# INPUT.net
KiCad netlist of a schematic drawn in Altium Designer
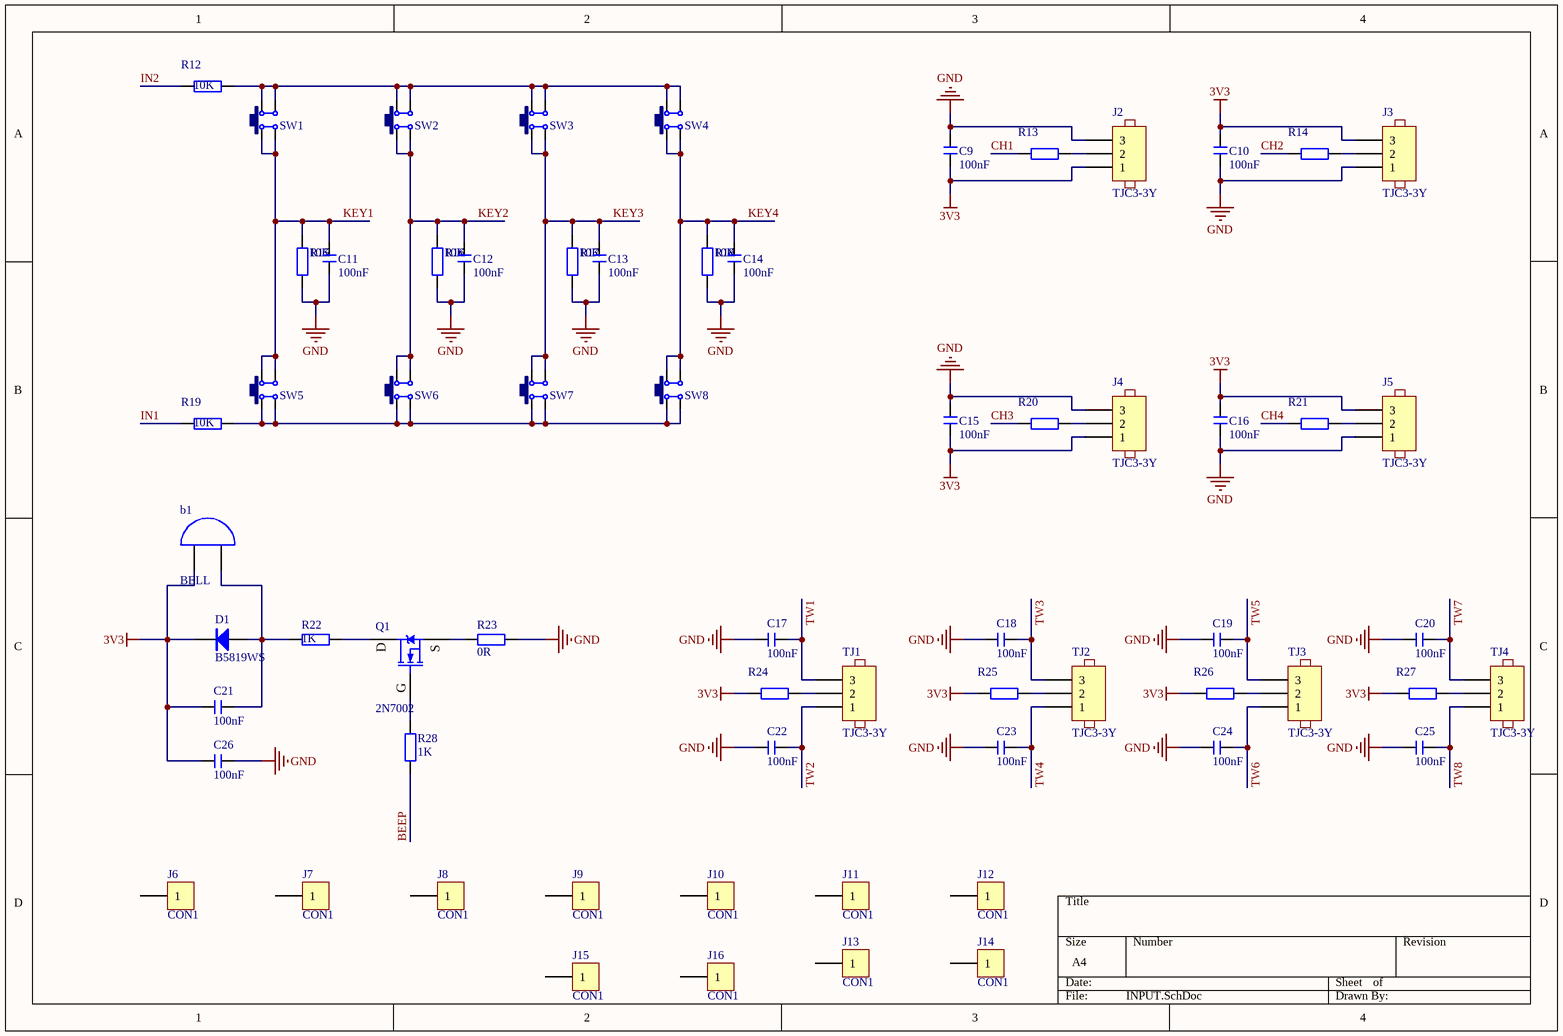
[diagram p0: INPUT.SchDoc]

(export (version "E")
  (design (tool "Eeschema 10.0.6"))
  (components
    (comp (ref "b1") (value "BELL") (footprint "BEEP 5x9x5.5") (libsource (lib "常用元件库") (part "BELL")))
    (comp (ref "C9")
      (value "100nF")
      (footprint "C 0603_L")
      (description "无极性贴片电容")
      (fields (field (name "版权归属") "源创客"))
      (libsource (lib "3.1   - 电阻-电容-电感") (part "C"))
    )
    (comp (ref "C10")
      (value "100nF")
      (footprint "C 0603_L")
      (description "无极性贴片电容")
      (fields (field (name "版权归属") "源创客"))
      (libsource (lib "3.1   - 电阻-电容-电感") (part "C"))
    )
    (comp (ref "C11")
      (value "100nF")
      (footprint "C 0603_L")
      (description "无极性贴片电容")
      (fields (field (name "版权归属") "源创客"))
      (libsource (lib "3.1   - 电阻-电容-电感") (part "C"))
    )
    (comp (ref "C12")
      (value "100nF")
      (footprint "C 0603_L")
      (description "无极性贴片电容")
      (fields (field (name "版权归属") "源创客"))
      (libsource (lib "3.1   - 电阻-电容-电感") (part "C"))
    )
    (comp (ref "C13")
      (value "100nF")
      (footprint "C 0603_L")
      (description "无极性贴片电容")
      (fields (field (name "版权归属") "源创客"))
      (libsource (lib "3.1   - 电阻-电容-电感") (part "C"))
    )
    (comp (ref "C14")
      (value "100nF")
      (footprint "C 0603_L")
      (description "无极性贴片电容")
      (fields (field (name "版权归属") "源创客"))
      (libsource (lib "3.1   - 电阻-电容-电感") (part "C"))
    )
    (comp (ref "C15")
      (value "100nF")
      (footprint "C 0603_L")
      (description "无极性贴片电容")
      (fields (field (name "版权归属") "源创客"))
      (libsource (lib "3.1   - 电阻-电容-电感") (part "C"))
    )
    (comp (ref "C16")
      (value "100nF")
      (footprint "C 0603_L")
      (description "无极性贴片电容")
      (fields (field (name "版权归属") "源创客"))
      (libsource (lib "3.1   - 电阻-电容-电感") (part "C"))
    )
    (comp (ref "C17")
      (value "100nF")
      (footprint "C 0603_L")
      (description "无极性贴片电容")
      (fields (field (name "版权归属") "源创客"))
      (libsource (lib "3.1   - 电阻-电容-电感") (part "C"))
    )
    (comp (ref "C18")
      (value "100nF")
      (footprint "C 0603_L")
      (description "无极性贴片电容")
      (fields (field (name "版权归属") "源创客"))
      (libsource (lib "3.1   - 电阻-电容-电感") (part "C"))
    )
    (comp (ref "C19")
      (value "100nF")
      (footprint "C 0603_L")
      (description "无极性贴片电容")
      (fields (field (name "版权归属") "源创客"))
      (libsource (lib "3.1   - 电阻-电容-电感") (part "C"))
    )
    (comp (ref "C20")
      (value "100nF")
      (footprint "C 0603_L")
      (description "无极性贴片电容")
      (fields (field (name "版权归属") "源创客"))
      (libsource (lib "3.1   - 电阻-电容-电感") (part "C"))
    )
    (comp (ref "C21")
      (value "100nF")
      (footprint "C 0603_L")
      (description "无极性贴片电容")
      (fields (field (name "版权归属") "源创客"))
      (libsource (lib "3.1   - 电阻-电容-电感") (part "C"))
    )
    (comp (ref "C22")
      (value "100nF")
      (footprint "C 0603_L")
      (description "无极性贴片电容")
      (fields (field (name "版权归属") "源创客"))
      (libsource (lib "3.1   - 电阻-电容-电感") (part "C"))
    )
    (comp (ref "C23")
      (value "100nF")
      (footprint "C 0603_L")
      (description "无极性贴片电容")
      (fields (field (name "版权归属") "源创客"))
      (libsource (lib "3.1   - 电阻-电容-电感") (part "C"))
    )
    (comp (ref "C24")
      (value "100nF")
      (footprint "C 0603_L")
      (description "无极性贴片电容")
      (fields (field (name "版权归属") "源创客"))
      (libsource (lib "3.1   - 电阻-电容-电感") (part "C"))
    )
    (comp (ref "C25")
      (value "100nF")
      (footprint "C 0603_L")
      (description "无极性贴片电容")
      (fields (field (name "版权归属") "源创客"))
      (libsource (lib "3.1   - 电阻-电容-电感") (part "C"))
    )
    (comp (ref "C26")
      (value "100nF")
      (footprint "C 0603_L")
      (description "无极性贴片电容")
      (fields (field (name "版权归属") "源创客"))
      (libsource (lib "3.1   - 电阻-电容-电感") (part "C"))
    )
    (comp (ref "D1")
      (value "B5819WS")
      (footprint "SOD-323")
      (description "肖特基二极管                           电压:40V 电流:1A                 C7420331")
      (fields (field (name "版权归属") "源创客"))
      (libsource (lib "8.1   - 二极管-整流桥") (part "SR540"))
    )
    (comp (ref "J2")
      (value "TJC3-3Y")
      (footprint "MX 1.25-LS-3P")
      (description "HCZZ0015-3             C7433469")
      (fields (field (name "PUBLISHER") "Altium Limited"))
      (libsource (lib "接口与插座") (part "TJC3-3Y"))
    )
    (comp (ref "J3")
      (value "TJC3-3Y")
      (footprint "MX 1.25-LS-3P")
      (description "HCZZ0015-3             C7433469")
      (fields (field (name "PUBLISHER") "Altium Limited"))
      (libsource (lib "接口与插座") (part "TJC3-3Y"))
    )
    (comp (ref "J4")
      (value "TJC3-3Y")
      (footprint "MX 1.25-LS-3P")
      (description "HCZZ0015-3             C7433469")
      (fields (field (name "PUBLISHER") "Altium Limited"))
      (libsource (lib "接口与插座") (part "TJC3-3Y"))
    )
    (comp (ref "J5")
      (value "TJC3-3Y")
      (footprint "MX 1.25-LS-3P")
      (description "HCZZ0015-3             C7433469")
      (fields (field (name "PUBLISHER") "Altium Limited"))
      (libsource (lib "接口与插座") (part "TJC3-3Y"))
    )
    (comp (ref "J6") (value "CON1") (footprint "M3x5+6_L") (libsource (lib "常用元件库") (part "CON1")))
    (comp (ref "J7") (value "CON1") (footprint "M3x5+6_L") (libsource (lib "常用元件库") (part "CON1")))
    (comp (ref "J8") (value "CON1") (footprint "M3x5+6_L") (libsource (lib "常用元件库") (part "CON1")))
    (comp (ref "J9") (value "CON1") (footprint "M3x5+6_L") (libsource (lib "常用元件库") (part "CON1")))
    (comp (ref "J10") (value "CON1") (footprint "M3x5+6_L") (libsource (lib "常用元件库") (part "CON1")))
    (comp (ref "J11") (value "CON1") (footprint "M3x5+6_L") (libsource (lib "常用元件库") (part "CON1")))
    (comp (ref "J12") (value "CON1") (footprint "M3x5+6_L") (libsource (lib "常用元件库") (part "CON1")))
    (comp (ref "J13") (value "CON1") (footprint "M3x5+6_L") (libsource (lib "常用元件库") (part "CON1")))
    (comp (ref "J14") (value "CON1") (footprint "M3x5+6_L") (libsource (lib "常用元件库") (part "CON1")))
    (comp (ref "J15") (value "CON1") (footprint "M3x5+6_L") (libsource (lib "常用元件库") (part "CON1")))
    (comp (ref "J16") (value "CON1") (footprint "M3x5+6_L") (libsource (lib "常用元件库") (part "CON1")))
    (comp (ref "Q1")
      (value "2N7002")
      (footprint "SOT-23")
      (description "N沟场效应管")
      (fields (field (name "版权归属") "源创客"))
      (libsource (lib "6.1   - 场效应管-可控硅") (part "IRF840"))
    )
    (comp (ref "R12")
      (value "10K")
      (footprint "R 0603_L")
      (description "贴片电阻")
      (fields (field (name "版权归属") "源创客"))
      (libsource (lib "3.1   - 电阻-电容-电感") (part "R"))
    )
    (comp (ref "R13")
      (value "~")
      (footprint "R 0603_L")
      (description "贴片电阻")
      (fields (field (name "版权归属") "源创客"))
      (libsource (lib "3.1   - 电阻-电容-电感") (part "R"))
    )
    (comp (ref "R14")
      (value "~")
      (footprint "R 0603_L")
      (description "贴片电阻")
      (fields (field (name "版权归属") "源创客"))
      (libsource (lib "3.1   - 电阻-电容-电感") (part "R"))
    )
    (comp (ref "R15")
      (value "10K")
      (footprint "R 0603_L")
      (description "贴片电阻")
      (fields (field (name "版权归属") "源创客"))
      (libsource (lib "3.1   - 电阻-电容-电感") (part "R"))
    )
    (comp (ref "R16")
      (value "10K")
      (footprint "R 0603_L")
      (description "贴片电阻")
      (fields (field (name "版权归属") "源创客"))
      (libsource (lib "3.1   - 电阻-电容-电感") (part "R"))
    )
    (comp (ref "R17")
      (value "10K")
      (footprint "R 0603_L")
      (description "贴片电阻")
      (fields (field (name "版权归属") "源创客"))
      (libsource (lib "3.1   - 电阻-电容-电感") (part "R"))
    )
    (comp (ref "R18")
      (value "10K")
      (footprint "R 0603_L")
      (description "贴片电阻")
      (fields (field (name "版权归属") "源创客"))
      (libsource (lib "3.1   - 电阻-电容-电感") (part "R"))
    )
    (comp (ref "R19")
      (value "10K")
      (footprint "R 0603_L")
      (description "贴片电阻")
      (fields (field (name "版权归属") "源创客"))
      (libsource (lib "3.1   - 电阻-电容-电感") (part "R"))
    )
    (comp (ref "R20")
      (value "~")
      (footprint "R 0603_L")
      (description "贴片电阻")
      (fields (field (name "版权归属") "源创客"))
      (libsource (lib "3.1   - 电阻-电容-电感") (part "R"))
    )
    (comp (ref "R21")
      (value "~")
      (footprint "R 0603_L")
      (description "贴片电阻")
      (fields (field (name "版权归属") "源创客"))
      (libsource (lib "3.1   - 电阻-电容-电感") (part "R"))
    )
    (comp (ref "R22")
      (value "1K")
      (footprint "R 0603_L")
      (description "贴片电阻")
      (fields (field (name "版权归属") "源创客"))
      (libsource (lib "3.1   - 电阻-电容-电感") (part "R"))
    )
    (comp (ref "R23")
      (value "0R")
      (footprint "R 0603_L")
      (description "贴片电阻")
      (fields (field (name "版权归属") "源创客"))
      (libsource (lib "3.1   - 电阻-电容-电感") (part "R"))
    )
    (comp (ref "R24")
      (value "~")
      (footprint "R 0603_L")
      (description "贴片电阻")
      (fields (field (name "版权归属") "源创客"))
      (libsource (lib "3.1   - 电阻-电容-电感") (part "R"))
    )
    (comp (ref "R25")
      (value "~")
      (footprint "R 0603_L")
      (description "贴片电阻")
      (fields (field (name "版权归属") "源创客"))
      (libsource (lib "3.1   - 电阻-电容-电感") (part "R"))
    )
    (comp (ref "R26")
      (value "~")
      (footprint "R 0603_L")
      (description "贴片电阻")
      (fields (field (name "版权归属") "源创客"))
      (libsource (lib "3.1   - 电阻-电容-电感") (part "R"))
    )
    (comp (ref "R27")
      (value "~")
      (footprint "R 0603_L")
      (description "贴片电阻")
      (fields (field (name "版权归属") "源创客"))
      (libsource (lib "3.1   - 电阻-电容-电感") (part "R"))
    )
    (comp (ref "R28")
      (value "1K")
      (footprint "R 0603_L")
      (description "贴片电阻")
      (fields (field (name "版权归属") "源创客"))
      (libsource (lib "3.1   - 电阻-电容-电感") (part "R"))
    )
    (comp (ref "SW1")
      (value "6x6x5")
      (footprint "TSW SMD-6*6*5-L")
      (description "KH-6X6X5H-STM     C2837531")
      (fields (field (name "版权归属") "源创客"))
      (libsource (lib "5.1   - 按键-开关") (part "TSW SMD-6x6"))
    )
    (comp (ref "SW2")
      (value "6x6x5")
      (footprint "TSW SMD-6*6*5-L")
      (description "KH-6X6X5H-STM     C2837531")
      (fields (field (name "版权归属") "源创客"))
      (libsource (lib "5.1   - 按键-开关") (part "TSW SMD-6x6"))
    )
    (comp (ref "SW3")
      (value "6x6x5")
      (footprint "TSW SMD-6*6*5-L")
      (description "KH-6X6X5H-STM     C2837531")
      (fields (field (name "版权归属") "源创客"))
      (libsource (lib "5.1   - 按键-开关") (part "TSW SMD-6x6"))
    )
    (comp (ref "SW4")
      (value "6x6x5")
      (footprint "TSW SMD-6*6*5-L")
      (description "KH-6X6X5H-STM     C2837531")
      (fields (field (name "版权归属") "源创客"))
      (libsource (lib "5.1   - 按键-开关") (part "TSW SMD-6x6"))
    )
    (comp (ref "SW5")
      (value "6x6x5")
      (footprint "TSW SMD-6*6*5-L")
      (description "KH-6X6X5H-STM     C2837531")
      (fields (field (name "版权归属") "源创客"))
      (libsource (lib "5.1   - 按键-开关") (part "TSW SMD-6x6"))
    )
    (comp (ref "SW6")
      (value "6x6x5")
      (footprint "TSW SMD-6*6*5-L")
      (description "KH-6X6X5H-STM     C2837531")
      (fields (field (name "版权归属") "源创客"))
      (libsource (lib "5.1   - 按键-开关") (part "TSW SMD-6x6"))
    )
    (comp (ref "SW7")
      (value "6x6x5")
      (footprint "TSW SMD-6*6*5-L")
      (description "KH-6X6X5H-STM     C2837531")
      (fields (field (name "版权归属") "源创客"))
      (libsource (lib "5.1   - 按键-开关") (part "TSW SMD-6x6"))
    )
    (comp (ref "SW8")
      (value "6x6x5")
      (footprint "TSW SMD-6*6*5-L")
      (description "KH-6X6X5H-STM     C2837531")
      (fields (field (name "版权归属") "源创客"))
      (libsource (lib "5.1   - 按键-开关") (part "TSW SMD-6x6"))
    )
    (comp (ref "TJ1")
      (value "TJC3-3Y")
      (footprint "MX 1.25-LS-3P")
      (description "HCZZ0015-3             C7433469")
      (fields (field (name "PUBLISHER") "Altium Limited"))
      (libsource (lib "接口与插座") (part "TJC3-3Y"))
    )
    (comp (ref "TJ2")
      (value "TJC3-3Y")
      (footprint "MX 1.25-LS-3P")
      (description "HCZZ0015-3             C7433469")
      (fields (field (name "PUBLISHER") "Altium Limited"))
      (libsource (lib "接口与插座") (part "TJC3-3Y"))
    )
    (comp (ref "TJ3")
      (value "TJC3-3Y")
      (footprint "MX 1.25-LS-3P")
      (description "HCZZ0015-3             C7433469")
      (fields (field (name "PUBLISHER") "Altium Limited"))
      (libsource (lib "接口与插座") (part "TJC3-3Y"))
    )
    (comp (ref "TJ4")
      (value "TJC3-3Y")
      (footprint "MX 1.25-LS-3P")
      (description "HCZZ0015-3             C7433469")
      (fields (field (name "PUBLISHER") "Altium Limited"))
      (libsource (lib "接口与插座") (part "TJC3-3Y"))
    )
  )
  (nets
    (net (code "1") (name "/BEEP") (class "Default")
      (node (ref "R28") (pin "1") (pinfunction "1_1") (pintype "passive"))
    )
    (net (code "2") (name "/CH1") (class "Default")
      (node (ref "R13") (pin "2") (pinfunction "2_2") (pintype "passive"))
    )
    (net (code "3") (name "/CH2") (class "Default")
      (node (ref "R14") (pin "2") (pinfunction "2_2") (pintype "passive"))
    )
    (net (code "4") (name "/CH3") (class "Default")
      (node (ref "R20") (pin "2") (pinfunction "2_2") (pintype "passive"))
    )
    (net (code "5") (name "/CH4") (class "Default")
      (node (ref "R21") (pin "2") (pinfunction "2_2") (pintype "passive"))
    )
    (net (code "6") (name "/IN1") (class "Default")
      (node (ref "R19") (pin "2") (pinfunction "2_2") (pintype "passive"))
    )
    (net (code "7") (name "/IN2") (class "Default")
      (node (ref "R12") (pin "2") (pinfunction "2_2") (pintype "passive"))
    )
    (net (code "8") (name "/KEY1") (class "Default")
      (node (ref "C11") (pin "2") (pinfunction "2_2") (pintype "passive"))
      (node (ref "R15") (pin "1") (pinfunction "1_1") (pintype "passive"))
      (node (ref "SW1") (pin "1") (pinfunction "1_1") (pintype "passive"))
      (node (ref "SW1") (pin "4") (pinfunction "4_4") (pintype "passive"))
      (node (ref "SW5") (pin "2") (pinfunction "2_2") (pintype "passive"))
      (node (ref "SW5") (pin "3") (pinfunction "3_3") (pintype "passive"))
    )
    (net (code "9") (name "/KEY2") (class "Default")
      (node (ref "C12") (pin "2") (pinfunction "2_2") (pintype "passive"))
      (node (ref "R16") (pin "1") (pinfunction "1_1") (pintype "passive"))
      (node (ref "SW2") (pin "1") (pinfunction "1_1") (pintype "passive"))
      (node (ref "SW2") (pin "4") (pinfunction "4_4") (pintype "passive"))
      (node (ref "SW6") (pin "2") (pinfunction "2_2") (pintype "passive"))
      (node (ref "SW6") (pin "3") (pinfunction "3_3") (pintype "passive"))
    )
    (net (code "10") (name "/KEY3") (class "Default")
      (node (ref "C13") (pin "2") (pinfunction "2_2") (pintype "passive"))
      (node (ref "R17") (pin "1") (pinfunction "1_1") (pintype "passive"))
      (node (ref "SW3") (pin "1") (pinfunction "1_1") (pintype "passive"))
      (node (ref "SW3") (pin "4") (pinfunction "4_4") (pintype "passive"))
      (node (ref "SW7") (pin "2") (pinfunction "2_2") (pintype "passive"))
      (node (ref "SW7") (pin "3") (pinfunction "3_3") (pintype "passive"))
    )
    (net (code "11") (name "/KEY4") (class "Default")
      (node (ref "C14") (pin "2") (pinfunction "2_2") (pintype "passive"))
      (node (ref "R18") (pin "1") (pinfunction "1_1") (pintype "passive"))
      (node (ref "SW4") (pin "1") (pinfunction "1_1") (pintype "passive"))
      (node (ref "SW4") (pin "4") (pinfunction "4_4") (pintype "passive"))
      (node (ref "SW8") (pin "2") (pinfunction "2_2") (pintype "passive"))
      (node (ref "SW8") (pin "3") (pinfunction "3_3") (pintype "passive"))
    )
    (net (code "12") (name "/TW1") (class "Default")
      (node (ref "C17") (pin "1") (pinfunction "1_1") (pintype "passive"))
      (node (ref "TJ1") (pin "3") (pinfunction "3_3") (pintype "passive"))
    )
    (net (code "13") (name "/TW2") (class "Default")
      (node (ref "C22") (pin "1") (pinfunction "1_1") (pintype "passive"))
      (node (ref "TJ1") (pin "1") (pinfunction "1_1") (pintype "passive"))
    )
    (net (code "14") (name "/TW3") (class "Default")
      (node (ref "C18") (pin "1") (pinfunction "1_1") (pintype "passive"))
      (node (ref "TJ2") (pin "3") (pinfunction "3_3") (pintype "passive"))
    )
    (net (code "15") (name "/TW4") (class "Default")
      (node (ref "C23") (pin "1") (pinfunction "1_1") (pintype "passive"))
      (node (ref "TJ2") (pin "1") (pinfunction "1_1") (pintype "passive"))
    )
    (net (code "16") (name "/TW5") (class "Default")
      (node (ref "C19") (pin "1") (pinfunction "1_1") (pintype "passive"))
      (node (ref "TJ3") (pin "3") (pinfunction "3_3") (pintype "passive"))
    )
    (net (code "17") (name "/TW6") (class "Default")
      (node (ref "C24") (pin "1") (pinfunction "1_1") (pintype "passive"))
      (node (ref "TJ3") (pin "1") (pinfunction "1_1") (pintype "passive"))
    )
    (net (code "18") (name "/TW7") (class "Default")
      (node (ref "C20") (pin "1") (pinfunction "1_1") (pintype "passive"))
      (node (ref "TJ4") (pin "3") (pinfunction "3_3") (pintype "passive"))
    )
    (net (code "19") (name "/TW8") (class "Default")
      (node (ref "C25") (pin "1") (pinfunction "1_1") (pintype "passive"))
      (node (ref "TJ4") (pin "1") (pinfunction "1_1") (pintype "passive"))
    )
    (net (code "20") (name "3V3") (class "Default")
      (node (ref "C10") (pin "2") (pinfunction "2_2") (pintype "passive"))
      (node (ref "C15") (pin "1") (pinfunction "1_1") (pintype "passive"))
      (node (ref "C16") (pin "2") (pinfunction "2_2") (pintype "passive"))
      (node (ref "C21") (pin "2") (pinfunction "2_2") (pintype "passive"))
      (node (ref "C26") (pin "2") (pinfunction "2_2") (pintype "passive"))
      (node (ref "C9") (pin "1") (pinfunction "1_1") (pintype "passive"))
      (node (ref "D1") (pin "2") (pinfunction "K_2") (pintype "passive"))
      (node (ref "J2") (pin "1") (pinfunction "1_1") (pintype "passive"))
      (node (ref "J3") (pin "3") (pinfunction "3_3") (pintype "passive"))
      (node (ref "J4") (pin "1") (pinfunction "1_1") (pintype "passive"))
      (node (ref "J5") (pin "3") (pinfunction "3_3") (pintype "passive"))
      (node (ref "R24") (pin "2") (pinfunction "2_2") (pintype "passive"))
      (node (ref "R25") (pin "2") (pinfunction "2_2") (pintype "passive"))
      (node (ref "R26") (pin "2") (pinfunction "2_2") (pintype "passive"))
      (node (ref "R27") (pin "2") (pinfunction "2_2") (pintype "passive"))
      (node (ref "b1") (pin "1") (pinfunction "1_1") (pintype "passive"))
    )
    (net (code "21") (name "GND") (class "Default")
      (node (ref "C10") (pin "1") (pinfunction "1_1") (pintype "passive"))
      (node (ref "C11") (pin "1") (pinfunction "1_1") (pintype "passive"))
      (node (ref "C12") (pin "1") (pinfunction "1_1") (pintype "passive"))
      (node (ref "C13") (pin "1") (pinfunction "1_1") (pintype "passive"))
      (node (ref "C14") (pin "1") (pinfunction "1_1") (pintype "passive"))
      (node (ref "C15") (pin "2") (pinfunction "2_2") (pintype "passive"))
      (node (ref "C16") (pin "1") (pinfunction "1_1") (pintype "passive"))
      (node (ref "C17") (pin "2") (pinfunction "2_2") (pintype "passive"))
      (node (ref "C18") (pin "2") (pinfunction "2_2") (pintype "passive"))
      (node (ref "C19") (pin "2") (pinfunction "2_2") (pintype "passive"))
      (node (ref "C20") (pin "2") (pinfunction "2_2") (pintype "passive"))
      (node (ref "C22") (pin "2") (pinfunction "2_2") (pintype "passive"))
      (node (ref "C23") (pin "2") (pinfunction "2_2") (pintype "passive"))
      (node (ref "C24") (pin "2") (pinfunction "2_2") (pintype "passive"))
      (node (ref "C25") (pin "2") (pinfunction "2_2") (pintype "passive"))
      (node (ref "C26") (pin "1") (pinfunction "1_1") (pintype "passive"))
      (node (ref "C9") (pin "2") (pinfunction "2_2") (pintype "passive"))
      (node (ref "J2") (pin "3") (pinfunction "3_3") (pintype "passive"))
      (node (ref "J3") (pin "1") (pinfunction "1_1") (pintype "passive"))
      (node (ref "J4") (pin "3") (pinfunction "3_3") (pintype "passive"))
      (node (ref "J5") (pin "1") (pinfunction "1_1") (pintype "passive"))
      (node (ref "R15") (pin "2") (pinfunction "2_2") (pintype "passive"))
      (node (ref "R16") (pin "2") (pinfunction "2_2") (pintype "passive"))
      (node (ref "R17") (pin "2") (pinfunction "2_2") (pintype "passive"))
      (node (ref "R18") (pin "2") (pinfunction "2_2") (pintype "passive"))
      (node (ref "R23") (pin "1") (pinfunction "1_1") (pintype "passive"))
    )
    (net (code "22") (name "Net-(D1-A)") (class "Default")
      (node (ref "C21") (pin "1") (pinfunction "1_1") (pintype "passive"))
      (node (ref "D1") (pin "1") (pinfunction "A_1") (pintype "passive"))
      (node (ref "R22") (pin "1") (pinfunction "1_1") (pintype "passive"))
      (node (ref "b1") (pin "2") (pinfunction "2_2") (pintype "passive"))
    )
    (net (code "23") (name "Net-(J2-Pad2)") (class "Default")
      (node (ref "J2") (pin "2") (pinfunction "2_2") (pintype "passive"))
      (node (ref "R13") (pin "1") (pinfunction "1_1") (pintype "passive"))
    )
    (net (code "24") (name "Net-(J3-Pad2)") (class "Default")
      (node (ref "J3") (pin "2") (pinfunction "2_2") (pintype "passive"))
      (node (ref "R14") (pin "1") (pinfunction "1_1") (pintype "passive"))
    )
    (net (code "25") (name "Net-(J4-Pad2)") (class "Default")
      (node (ref "J4") (pin "2") (pinfunction "2_2") (pintype "passive"))
      (node (ref "R20") (pin "1") (pinfunction "1_1") (pintype "passive"))
    )
    (net (code "26") (name "Net-(J5-Pad2)") (class "Default")
      (node (ref "J5") (pin "2") (pinfunction "2_2") (pintype "passive"))
      (node (ref "R21") (pin "1") (pinfunction "1_1") (pintype "passive"))
    )
    (net (code "27") (name "Net-(Q1-D)") (class "Default")
      (node (ref "Q1") (pin "2") (pinfunction "D_2") (pintype "passive"))
      (node (ref "R22") (pin "2") (pinfunction "2_2") (pintype "passive"))
    )
    (net (code "28") (name "Net-(Q1-G)") (class "Default")
      (node (ref "Q1") (pin "1") (pinfunction "G_1") (pintype "passive"))
      (node (ref "R28") (pin "2") (pinfunction "2_2") (pintype "passive"))
    )
    (net (code "29") (name "Net-(Q1-S)") (class "Default")
      (node (ref "Q1") (pin "3") (pinfunction "S_3") (pintype "passive"))
      (node (ref "R23") (pin "2") (pinfunction "2_2") (pintype "passive"))
    )
    (net (code "30") (name "Net-(R12-Pad1)") (class "Default")
      (node (ref "R12") (pin "1") (pinfunction "1_1") (pintype "passive"))
      (node (ref "SW1") (pin "2") (pinfunction "2_2") (pintype "passive"))
      (node (ref "SW1") (pin "3") (pinfunction "3_3") (pintype "passive"))
      (node (ref "SW2") (pin "2") (pinfunction "2_2") (pintype "passive"))
      (node (ref "SW2") (pin "3") (pinfunction "3_3") (pintype "passive"))
      (node (ref "SW3") (pin "2") (pinfunction "2_2") (pintype "passive"))
      (node (ref "SW3") (pin "3") (pinfunction "3_3") (pintype "passive"))
      (node (ref "SW4") (pin "2") (pinfunction "2_2") (pintype "passive"))
      (node (ref "SW4") (pin "3") (pinfunction "3_3") (pintype "passive"))
    )
    (net (code "31") (name "Net-(R19-Pad1)") (class "Default")
      (node (ref "R19") (pin "1") (pinfunction "1_1") (pintype "passive"))
      (node (ref "SW5") (pin "1") (pinfunction "1_1") (pintype "passive"))
      (node (ref "SW5") (pin "4") (pinfunction "4_4") (pintype "passive"))
      (node (ref "SW6") (pin "1") (pinfunction "1_1") (pintype "passive"))
      (node (ref "SW6") (pin "4") (pinfunction "4_4") (pintype "passive"))
      (node (ref "SW7") (pin "1") (pinfunction "1_1") (pintype "passive"))
      (node (ref "SW7") (pin "4") (pinfunction "4_4") (pintype "passive"))
      (node (ref "SW8") (pin "1") (pinfunction "1_1") (pintype "passive"))
      (node (ref "SW8") (pin "4") (pinfunction "4_4") (pintype "passive"))
    )
    (net (code "32") (name "Net-(R24-Pad1)") (class "Default")
      (node (ref "R24") (pin "1") (pinfunction "1_1") (pintype "passive"))
      (node (ref "TJ1") (pin "2") (pinfunction "2_2") (pintype "passive"))
    )
    (net (code "33") (name "Net-(R25-Pad1)") (class "Default")
      (node (ref "R25") (pin "1") (pinfunction "1_1") (pintype "passive"))
      (node (ref "TJ2") (pin "2") (pinfunction "2_2") (pintype "passive"))
    )
    (net (code "34") (name "Net-(R26-Pad1)") (class "Default")
      (node (ref "R26") (pin "1") (pinfunction "1_1") (pintype "passive"))
      (node (ref "TJ3") (pin "2") (pinfunction "2_2") (pintype "passive"))
    )
    (net (code "35") (name "Net-(R27-Pad1)") (class "Default")
      (node (ref "R27") (pin "1") (pinfunction "1_1") (pintype "passive"))
      (node (ref "TJ4") (pin "2") (pinfunction "2_2") (pintype "passive"))
    )
    (net (code "36") (name "unconnected-(J6-Pad1)") (class "Default")
      (node (ref "J6") (pin "1") (pinfunction "1_1") (pintype "passive"))
    )
    (net (code "37") (name "unconnected-(J7-Pad1)") (class "Default")
      (node (ref "J7") (pin "1") (pinfunction "1_1") (pintype "passive"))
    )
    (net (code "38") (name "unconnected-(J8-Pad1)") (class "Default")
      (node (ref "J8") (pin "1") (pinfunction "1_1") (pintype "passive"))
    )
    (net (code "39") (name "unconnected-(J9-Pad1)") (class "Default")
      (node (ref "J9") (pin "1") (pinfunction "1_1") (pintype "passive"))
    )
    (net (code "40") (name "unconnected-(J10-Pad1)") (class "Default")
      (node (ref "J10") (pin "1") (pinfunction "1_1") (pintype "passive"))
    )
    (net (code "41") (name "unconnected-(J11-Pad1)") (class "Default")
      (node (ref "J11") (pin "1") (pinfunction "1_1") (pintype "passive"))
    )
    (net (code "42") (name "unconnected-(J12-Pad1)") (class "Default")
      (node (ref "J12") (pin "1") (pinfunction "1_1") (pintype "passive"))
    )
    (net (code "43") (name "unconnected-(J13-Pad1)") (class "Default")
      (node (ref "J13") (pin "1") (pinfunction "1_1") (pintype "passive"))
    )
    (net (code "44") (name "unconnected-(J14-Pad1)") (class "Default")
      (node (ref "J14") (pin "1") (pinfunction "1_1") (pintype "passive"))
    )
    (net (code "45") (name "unconnected-(J15-Pad1)") (class "Default")
      (node (ref "J15") (pin "1") (pinfunction "1_1") (pintype "passive"))
    )
    (net (code "46") (name "unconnected-(J16-Pad1)") (class "Default")
      (node (ref "J16") (pin "1") (pinfunction "1_1") (pintype "passive"))
    )
  )
)
